# Ex_4_LED_FadeInOut.net
KiCad netlist of a schematic drawn in EAGLE
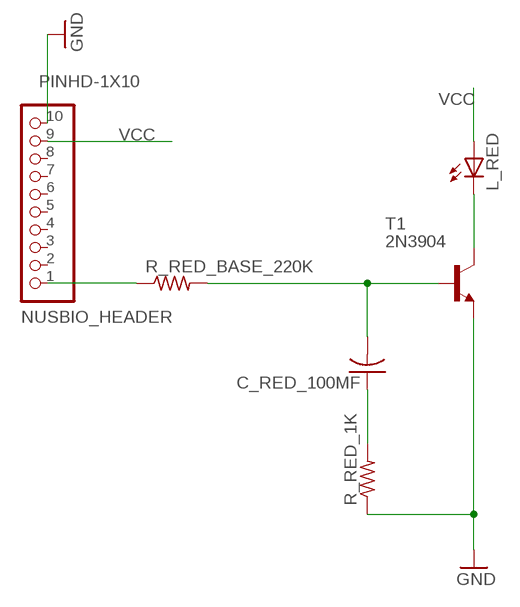
[diagram p0: schematic, sheet 1]

(export (version "E")
  (design (tool "Eeschema 10.0.6"))
  (components
    (comp (ref "C_RED_100MF")
      (value "C-US025-030X050")
      (footprint "eagle-import:C025-030X050")
      (libsource (lib "eagle-import") (part "C-US025-030X050"))
    )
    (comp (ref "L_RED")
      (value "LED5MM")
      (footprint "eagle-import:LED5MM")
      (libsource (lib "eagle-import") (part "LED5MM"))
    )
    (comp (ref "NUSBIO_HEADER")
      (value "PINHD-1X10")
      (footprint "eagle-import:1X10-BIG")
      (libsource (lib "eagle-import") (part "PINHD-1X10"))
    )
    (comp (ref "R_RED_1K")
      (value "R-US_0207/10")
      (footprint "eagle-import:0207_10")
      (libsource (lib "eagle-import") (part "R-US_0207/10"))
    )
    (comp (ref "R_RED_BASE_220K")
      (value "R-US_0207/10")
      (footprint "eagle-import:0207_10")
      (libsource (lib "eagle-import") (part "R-US_0207/10"))
    )
    (comp (ref "T1")
      (value "2N3904")
      (footprint "eagle-import:TO92")
      (libsource (lib "eagle-import") (part "2N3904"))
    )
  )
  (nets
    (net (code "1") (name "/VCC") (class "Default")
      (node (ref "L_RED") (pin "A") (pinfunction "A_A") (pintype "passive"))
      (node (ref "NUSBIO_HEADER") (pin "9") (pinfunction "9_9") (pintype "passive"))
    )
    (net (code "2") (name "GND") (class "Default")
      (node (ref "NUSBIO_HEADER") (pin "10") (pinfunction "10_10") (pintype "passive"))
      (node (ref "R_RED_1K") (pin "1") (pinfunction "1_1") (pintype "passive"))
      (node (ref "T1") (pin "3") (pinfunction "E_3") (pintype "passive"))
    )
    (net (code "3") (name "Net-(C_RED_100MF-Pad1)") (class "Default")
      (node (ref "C_RED_100MF") (pin "1") (pinfunction "1_1") (pintype "passive"))
      (node (ref "R_RED_1K") (pin "2") (pinfunction "2_2") (pintype "passive"))
    )
    (net (code "4") (name "Net-(L_RED-C)") (class "Default")
      (node (ref "L_RED") (pin "K") (pinfunction "C_K") (pintype "passive"))
      (node (ref "T1") (pin "1") (pinfunction "C_1") (pintype "passive"))
    )
    (net (code "5") (name "Net-(NUSBIO_HEADER-Pad1)") (class "Default")
      (node (ref "NUSBIO_HEADER") (pin "1") (pinfunction "1_1") (pintype "passive"))
      (node (ref "R_RED_BASE_220K") (pin "1") (pinfunction "1_1") (pintype "passive"))
    )
    (net (code "6") (name "Net-(T1-B)") (class "Default")
      (node (ref "C_RED_100MF") (pin "2") (pinfunction "2_2") (pintype "passive"))
      (node (ref "R_RED_BASE_220K") (pin "2") (pinfunction "2_2") (pintype "passive"))
      (node (ref "T1") (pin "2") (pinfunction "B_2") (pintype "passive"))
    )
    (net (code "7") (name "unconnected-(NUSBIO_HEADER-Pad2)") (class "Default")
      (node (ref "NUSBIO_HEADER") (pin "2") (pinfunction "2_2") (pintype "passive"))
    )
    (net (code "8") (name "unconnected-(NUSBIO_HEADER-Pad3)") (class "Default")
      (node (ref "NUSBIO_HEADER") (pin "3") (pinfunction "3_3") (pintype "passive"))
    )
    (net (code "9") (name "unconnected-(NUSBIO_HEADER-Pad4)") (class "Default")
      (node (ref "NUSBIO_HEADER") (pin "4") (pinfunction "4_4") (pintype "passive"))
    )
    (net (code "10") (name "unconnected-(NUSBIO_HEADER-Pad5)") (class "Default")
      (node (ref "NUSBIO_HEADER") (pin "5") (pinfunction "5_5") (pintype "passive"))
    )
    (net (code "11") (name "unconnected-(NUSBIO_HEADER-Pad6)") (class "Default")
      (node (ref "NUSBIO_HEADER") (pin "6") (pinfunction "6_6") (pintype "passive"))
    )
    (net (code "12") (name "unconnected-(NUSBIO_HEADER-Pad7)") (class "Default")
      (node (ref "NUSBIO_HEADER") (pin "7") (pinfunction "7_7") (pintype "passive"))
    )
    (net (code "13") (name "unconnected-(NUSBIO_HEADER-Pad8)") (class "Default")
      (node (ref "NUSBIO_HEADER") (pin "8") (pinfunction "8_8") (pintype "passive"))
    )
  )
)
